# CCM_0005.net
KiCad netlist of a schematic drawn in EAGLE
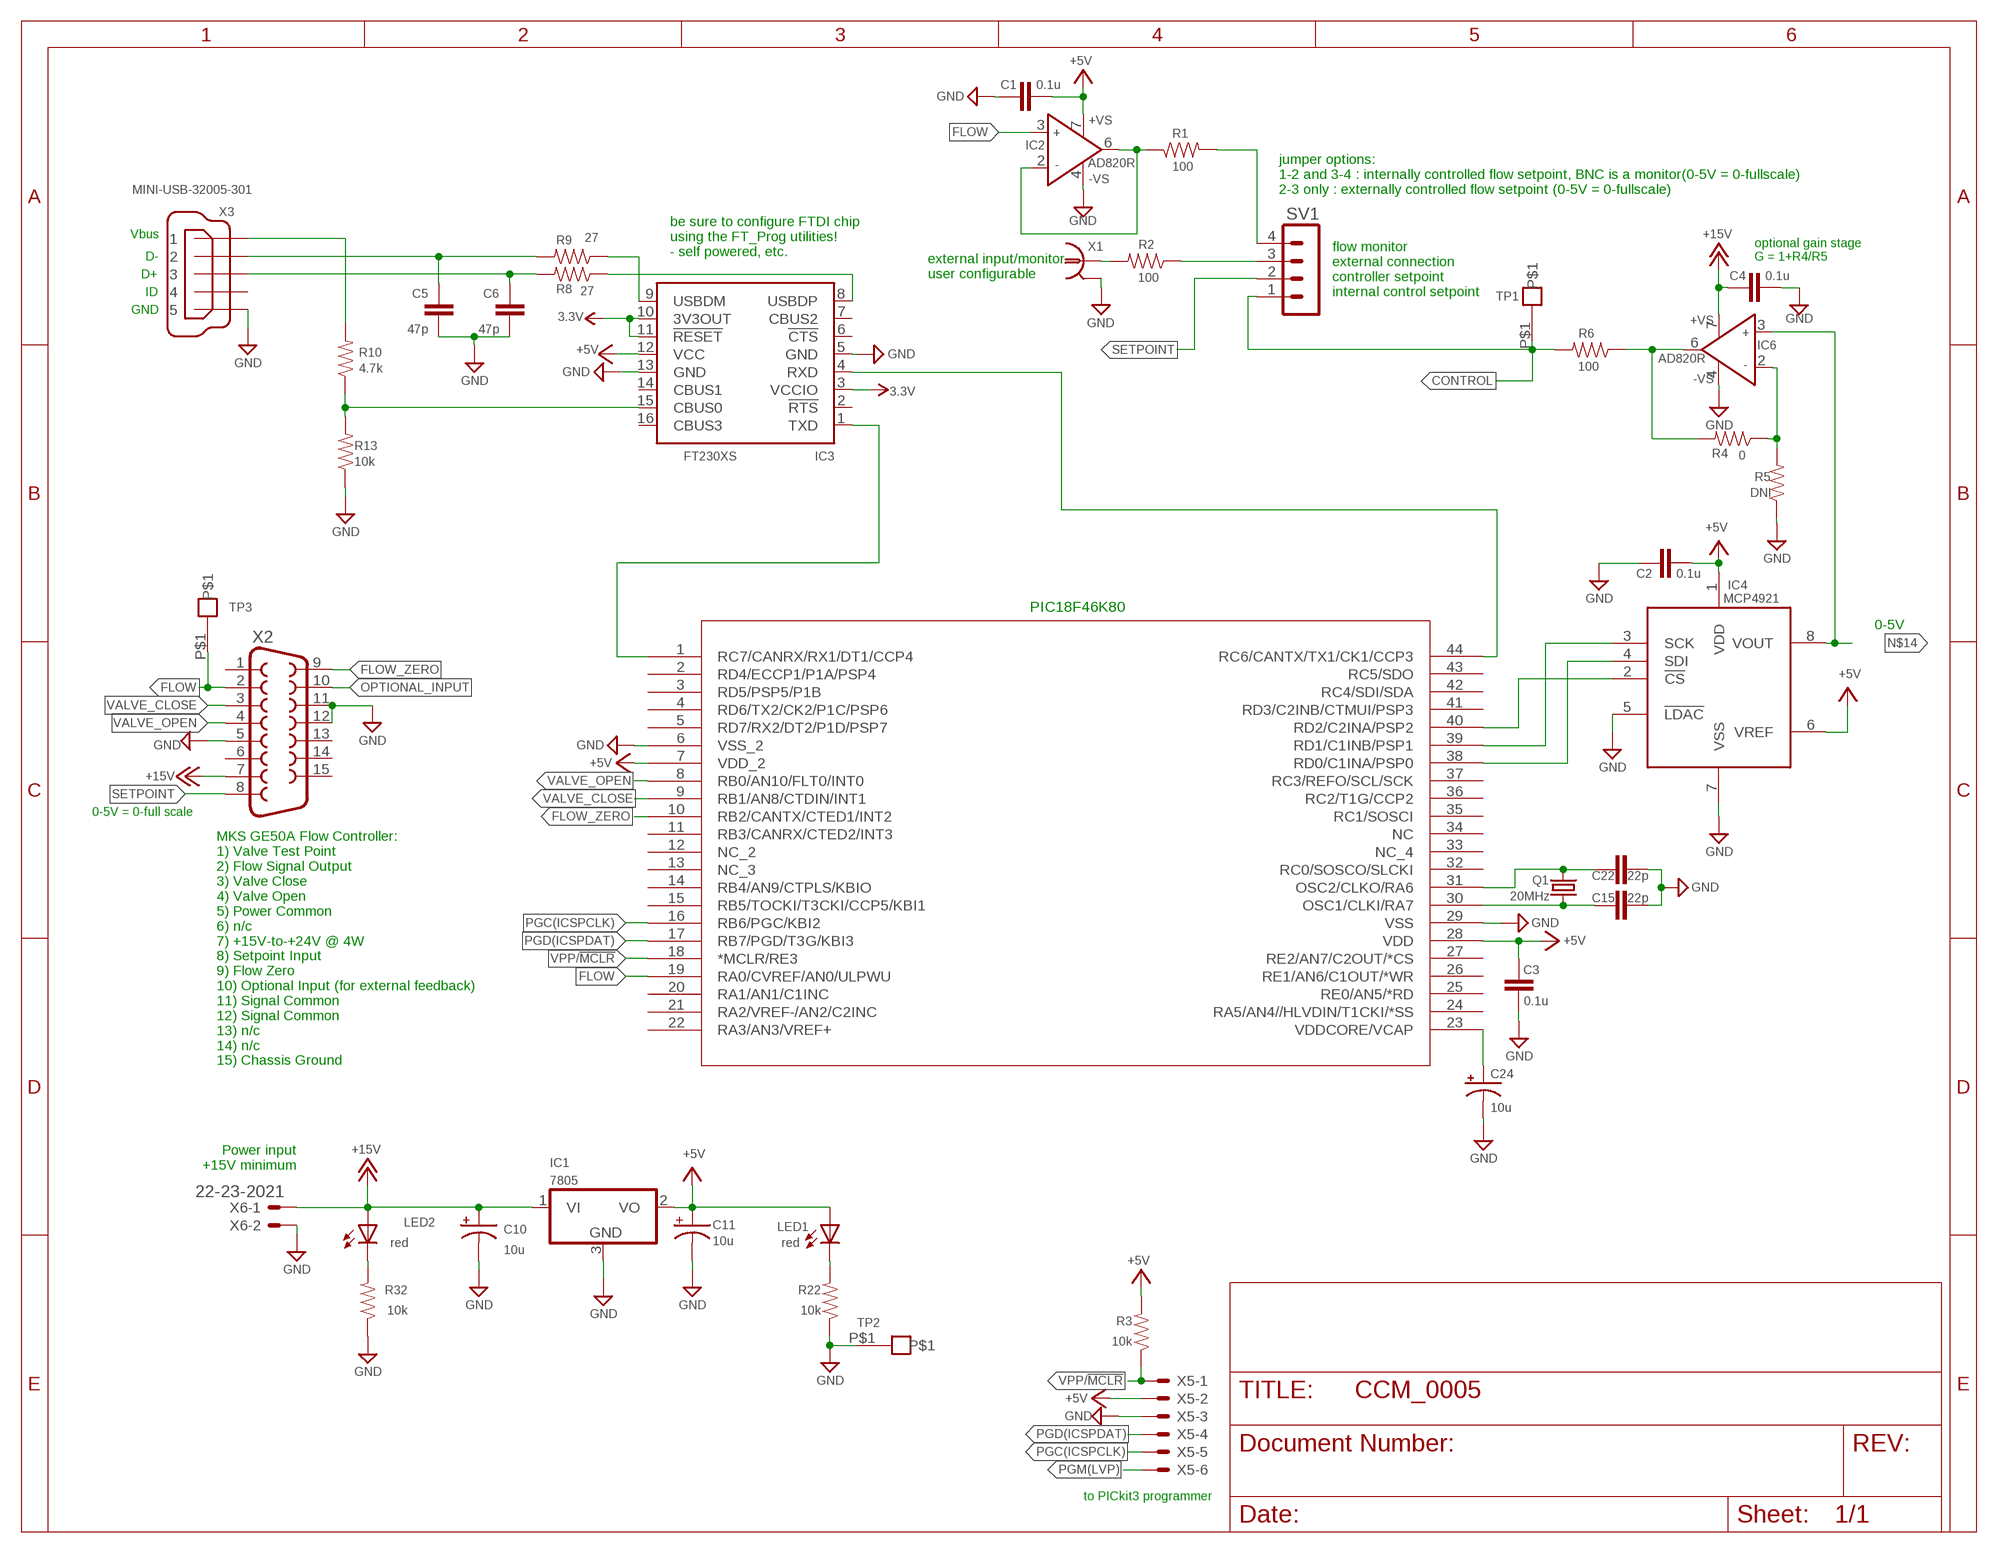
[diagram p0: schematic, sheet 1]

(export (version "E")
  (design (tool "Eeschema 10.0.6"))
  (components
    (comp (ref "C1")
      (value "0.1u")
      (footprint "eagle-import:0603-CAP")
      (libsource (lib "eagle-import") (part "CAP0603-CAP"))
    )
    (comp (ref "C2")
      (value "0.1u")
      (footprint "eagle-import:0603-CAP")
      (libsource (lib "eagle-import") (part "CAP0603-CAP"))
    )
    (comp (ref "C3")
      (value "0.1u")
      (footprint "eagle-import:0603-CAP")
      (libsource (lib "eagle-import") (part "CAP0603-CAP"))
    )
    (comp (ref "C4")
      (value "0.1u")
      (footprint "eagle-import:0603-CAP")
      (libsource (lib "eagle-import") (part "CAP0603-CAP"))
    )
    (comp (ref "C5")
      (value "47p")
      (footprint "eagle-import:0603-CAP")
      (libsource (lib "eagle-import") (part "CAP0603-CAP"))
    )
    (comp (ref "C6")
      (value "47p")
      (footprint "eagle-import:0603-CAP")
      (libsource (lib "eagle-import") (part "CAP0603-CAP"))
    )
    (comp (ref "C10")
      (value "10u")
      (footprint "eagle-import:EIA3216")
      (libsource (lib "eagle-import") (part "CAP_POL1206"))
    )
    (comp (ref "C11")
      (value "10u")
      (footprint "eagle-import:EIA3216")
      (libsource (lib "eagle-import") (part "CAP_POL1206"))
    )
    (comp (ref "C15")
      (value "22p")
      (footprint "eagle-import:0603-CAP")
      (libsource (lib "eagle-import") (part "CAP0603-CAP"))
    )
    (comp (ref "C22")
      (value "22p")
      (footprint "eagle-import:0603-CAP")
      (libsource (lib "eagle-import") (part "CAP0603-CAP"))
    )
    (comp (ref "C24")
      (value "10u")
      (footprint "eagle-import:EIA3216")
      (libsource (lib "eagle-import") (part "CAP_POL1206"))
    )
    (comp (ref "IC1")
      (value "7805")
      (footprint "eagle-import:TO252")
      (libsource (lib "eagle-import") (part "78DT24"))
    )
    (comp (ref "IC2")
      (value "AD820R")
      (footprint "eagle-import:SO8")
      (libsource (lib "eagle-import") (part "AD820R"))
    )
    (comp (ref "IC3")
      (value "FT230XS")
      (footprint "eagle-import:SSOP16")
      (libsource (lib "eagle-import") (part "FT230XS"))
    )
    (comp (ref "IC4")
      (value "MCP4921")
      (footprint "eagle-import:SO08")
      (libsource (lib "eagle-import") (part "MCP4921"))
    )
    (comp (ref "IC5")
      (value "PIC18F46K80")
      (footprint "eagle-import:TQFP44_MC")
      (libsource (lib "eagle-import") (part "PIC18F46K80"))
    )
    (comp (ref "IC6")
      (value "AD820R")
      (footprint "eagle-import:SO8")
      (libsource (lib "eagle-import") (part "AD820R"))
    )
    (comp (ref "LED1")
      (value "red")
      (footprint "eagle-import:CHIPLED_0603")
      (libsource (lib "eagle-import") (part "LEDCHIPLED_0603"))
    )
    (comp (ref "LED2")
      (value "red")
      (footprint "eagle-import:CHIPLED_0603")
      (libsource (lib "eagle-import") (part "LEDCHIPLED_0603"))
    )
    (comp (ref "Q1")
      (value "20MHz")
      (footprint "eagle-import:TC26V")
      (libsource (lib "eagle-import") (part "CRYSTALTC26V"))
    )
    (comp (ref "R1")
      (value "100")
      (footprint "eagle-import:0603-RES")
      (libsource (lib "eagle-import") (part "RESISTOR0603-RES"))
    )
    (comp (ref "R2")
      (value "100")
      (footprint "eagle-import:0603-RES")
      (libsource (lib "eagle-import") (part "RESISTOR0603-RES"))
    )
    (comp (ref "R3")
      (value "10k")
      (footprint "eagle-import:0603-RES")
      (libsource (lib "eagle-import") (part "RESISTOR0603-RES"))
    )
    (comp (ref "R4")
      (value "0")
      (footprint "eagle-import:0603-RES")
      (libsource (lib "eagle-import") (part "RESISTOR0603-RES"))
    )
    (comp (ref "R5")
      (value "DNI")
      (footprint "eagle-import:0603-RES")
      (libsource (lib "eagle-import") (part "RESISTOR0603-RES"))
    )
    (comp (ref "R6")
      (value "100")
      (footprint "eagle-import:0603-RES")
      (libsource (lib "eagle-import") (part "RESISTOR0603-RES"))
    )
    (comp (ref "R8")
      (value "27")
      (footprint "eagle-import:0603-RES")
      (libsource (lib "eagle-import") (part "RESISTOR0603-RES"))
    )
    (comp (ref "R9")
      (value "27")
      (footprint "eagle-import:0603-RES")
      (libsource (lib "eagle-import") (part "RESISTOR0603-RES"))
    )
    (comp (ref "R10")
      (value "4.7k")
      (footprint "eagle-import:0603-RES")
      (libsource (lib "eagle-import") (part "RESISTOR0603-RES"))
    )
    (comp (ref "R13")
      (value "10k")
      (footprint "eagle-import:0603-RES")
      (libsource (lib "eagle-import") (part "RESISTOR0603-RES"))
    )
    (comp (ref "R22")
      (value "10k")
      (footprint "eagle-import:0603-RES")
      (libsource (lib "eagle-import") (part "RESISTOR0603-RES"))
    )
    (comp (ref "R32")
      (value "10k")
      (footprint "eagle-import:0603-RES")
      (libsource (lib "eagle-import") (part "RESISTOR0603-RES"))
    )
    (comp (ref "SV1")
      (value "MA04-1")
      (footprint "eagle-import:MA04-1")
      (libsource (lib "eagle-import") (part "MA04-1"))
    )
    (comp (ref "TP1")
      (value "control")
      (footprint "eagle-import:TESTPOINT")
      (libsource (lib "eagle-import") (part "TESTPOINT"))
    )
    (comp (ref "TP2")
      (value "TESTPOINT")
      (footprint "eagle-import:TESTPOINT")
      (libsource (lib "eagle-import") (part "TESTPOINT"))
    )
    (comp (ref "TP3")
      (value "control")
      (footprint "eagle-import:TESTPOINT")
      (libsource (lib "eagle-import") (part "TESTPOINT"))
    )
    (comp (ref "X1")
      (value "1-227161-0")
      (footprint "eagle-import:AMP_227161")
      (fields (field (name "MF") "TYCO ELECTRONICS") (field (name "MPN") "1-227161"))
      (libsource (lib "eagle-import") (part "?2271611--0"))
    )
    (comp (ref "X2")
      (value "F15HP")
      (footprint "eagle-import:F15HP")
      (libsource (lib "eagle-import") (part "F15HP"))
    )
    (comp (ref "X3")
      (value "MINI-USB-32005-301")
      (footprint "eagle-import:32005-301")
      (libsource (lib "eagle-import") (part "MINI-USB-32005-301"))
    )
    (comp (ref "X5")
      (value "22-23-2061")
      (footprint "eagle-import:22-23-2061")
      (fields (field (name "MF") "MOLEX"))
      (libsource (lib "eagle-import") (part "22-23-2061"))
    )
    (comp (ref "X6")
      (value "22-23-2021")
      (footprint "eagle-import:22-23-2021")
      (fields (field (name "MF") "MOLEX"))
      (libsource (lib "eagle-import") (part "22-23-2021"))
    )
  )
  (nets
    (net (code "1") (name "+5V") (class "Default")
      (node (ref "C1") (pin "1") (pinfunction "1_1") (pintype "passive"))
      (node (ref "C11") (pin "A") (pinfunction "+_A") (pintype "passive"))
      (node (ref "C2") (pin "1") (pinfunction "1_1") (pintype "passive"))
      (node (ref "C3") (pin "1") (pinfunction "1_1") (pintype "passive"))
      (node (ref "IC1") (pin "2") (pinfunction "VO_2") (pintype "passive"))
      (node (ref "IC2") (pin "7") (pinfunction "+VS_7") (pintype "input"))
      (node (ref "IC3") (pin "12") (pinfunction "VCC_12") (pintype "power_in"))
      (node (ref "IC4") (pin "1") (pinfunction "VDD_1") (pintype "bidirectional"))
      (node (ref "IC4") (pin "6") (pinfunction "VREF_6") (pintype "bidirectional"))
      (node (ref "IC5") (pin "28") (pinfunction "VDD_28") (pintype "passive"))
      (node (ref "IC5") (pin "7") (pinfunction "VDD_2_7") (pintype "passive"))
      (node (ref "LED1") (pin "A") (pinfunction "A_A") (pintype "passive"))
      (node (ref "R3") (pin "2") (pinfunction "2_2") (pintype "passive"))
      (node (ref "X5") (pin "2") (pinfunction "S_2") (pintype "passive"))
    )
    (net (code "2") (name "+15V") (class "Default")
      (node (ref "C10") (pin "A") (pinfunction "+_A") (pintype "passive"))
      (node (ref "C4") (pin "2") (pinfunction "2_2") (pintype "passive"))
      (node (ref "IC1") (pin "1") (pinfunction "VI_1") (pintype "input"))
      (node (ref "IC6") (pin "7") (pinfunction "+VS_7") (pintype "input"))
      (node (ref "LED2") (pin "A") (pinfunction "A_A") (pintype "passive"))
      (node (ref "X2") (pin "7") (pinfunction "7_7") (pintype "passive"))
      (node (ref "X6") (pin "1") (pinfunction "S_1") (pintype "passive"))
    )
    (net (code "3") (name "/VPP{slash}~{MCLR}") (class "Default")
      (node (ref "IC5") (pin "18") (pinfunction "*MCLR/RE3_18") (pintype "passive"))
      (node (ref "R3") (pin "1") (pinfunction "1_1") (pintype "passive"))
      (node (ref "X5") (pin "1") (pinfunction "S_1") (pintype "passive"))
    )
    (net (code "4") (name "3.3V") (class "Default")
      (node (ref "IC3") (pin "10") (pinfunction "3V3OUT_10") (pintype "output"))
      (node (ref "IC3") (pin "11") (pinfunction "~{RESET}_11") (pintype "input"))
      (node (ref "IC3") (pin "3") (pinfunction "VCCIO_3") (pintype "power_in"))
    )
    (net (code "5") (name "CONTROL") (class "Default")
      (node (ref "R6") (pin "2") (pinfunction "2_2") (pintype "passive"))
      (node (ref "SV1") (pin "1") (pinfunction "1_1") (pintype "passive"))
      (node (ref "TP1") (pin "P$1") (pinfunction "P$1_P$1") (pintype "bidirectional"))
    )
    (net (code "6") (name "FLOW") (class "Default")
      (node (ref "IC2") (pin "3") (pinfunction "IN+_3") (pintype "input"))
      (node (ref "IC5") (pin "19") (pinfunction "RA0/CVREF/AN0/ULPWU_19") (pintype "passive"))
      (node (ref "TP3") (pin "P$1") (pinfunction "P$1_P$1") (pintype "bidirectional"))
      (node (ref "X2") (pin "2") (pinfunction "2_2") (pintype "passive"))
    )
    (net (code "7") (name "FLOW_ZERO") (class "Default")
      (node (ref "IC5") (pin "10") (pinfunction "RB2/CANTX/CTED1/INT2_10") (pintype "passive"))
      (node (ref "X2") (pin "9") (pinfunction "9_9") (pintype "passive"))
    )
    (net (code "8") (name "GND") (class "Default")
      (node (ref "C1") (pin "2") (pinfunction "2_2") (pintype "passive"))
      (node (ref "C10") (pin "C") (pinfunction "-_C") (pintype "passive"))
      (node (ref "C11") (pin "C") (pinfunction "-_C") (pintype "passive"))
      (node (ref "C15") (pin "1") (pinfunction "1_1") (pintype "passive"))
      (node (ref "C2") (pin "2") (pinfunction "2_2") (pintype "passive"))
      (node (ref "C22") (pin "1") (pinfunction "1_1") (pintype "passive"))
      (node (ref "C24") (pin "C") (pinfunction "-_C") (pintype "passive"))
      (node (ref "C3") (pin "2") (pinfunction "2_2") (pintype "passive"))
      (node (ref "C4") (pin "1") (pinfunction "1_1") (pintype "passive"))
      (node (ref "C5") (pin "2") (pinfunction "2_2") (pintype "passive"))
      (node (ref "C6") (pin "2") (pinfunction "2_2") (pintype "passive"))
      (node (ref "IC1") (pin "3") (pinfunction "GND_3") (pintype "passive"))
      (node (ref "IC2") (pin "4") (pinfunction "-VS_4") (pintype "input"))
      (node (ref "IC3") (pin "13") (pinfunction "GND_13") (pintype "power_in"))
      (node (ref "IC3") (pin "5") (pinfunction "GND_5") (pintype "power_in"))
      (node (ref "IC4") (pin "5") (pinfunction "~{LDAC}_5") (pintype "bidirectional"))
      (node (ref "IC4") (pin "7") (pinfunction "VSS_7") (pintype "bidirectional"))
      (node (ref "IC5") (pin "29") (pinfunction "VSS_29") (pintype "passive"))
      (node (ref "IC5") (pin "6") (pinfunction "VSS_2_6") (pintype "passive"))
      (node (ref "IC6") (pin "4") (pinfunction "-VS_4") (pintype "input"))
      (node (ref "R13") (pin "1") (pinfunction "1_1") (pintype "passive"))
      (node (ref "R22") (pin "1") (pinfunction "1_1") (pintype "passive"))
      (node (ref "R32") (pin "1") (pinfunction "1_1") (pintype "passive"))
      (node (ref "R5") (pin "1") (pinfunction "1_1") (pintype "passive"))
      (node (ref "TP2") (pin "P$1") (pinfunction "P$1_P$1") (pintype "bidirectional"))
      (node (ref "X1") (pin "2") (pinfunction "2_2") (pintype "passive"))
      (node (ref "X2") (pin "11") (pinfunction "11_11") (pintype "passive"))
      (node (ref "X2") (pin "12") (pinfunction "12_12") (pintype "passive"))
      (node (ref "X2") (pin "5") (pinfunction "5_5") (pintype "passive"))
      (node (ref "X3") (pin "5") (pinfunction "5_5") (pintype "passive"))
      (node (ref "X5") (pin "3") (pinfunction "S_3") (pintype "passive"))
      (node (ref "X6") (pin "2") (pinfunction "S_2") (pintype "passive"))
    )
    (net (code "9") (name "N$14") (class "Default")
      (node (ref "IC4") (pin "8") (pinfunction "VOUT_8") (pintype "bidirectional"))
      (node (ref "IC6") (pin "3") (pinfunction "IN+_3") (pintype "input"))
    )
    (net (code "10") (name "Net-(C5-Pad1)") (class "Default")
      (node (ref "C5") (pin "1") (pinfunction "1_1") (pintype "passive"))
      (node (ref "R9") (pin "2") (pinfunction "2_2") (pintype "passive"))
      (node (ref "X3") (pin "2") (pinfunction "2_2") (pintype "passive"))
    )
    (net (code "11") (name "Net-(C6-Pad1)") (class "Default")
      (node (ref "C6") (pin "1") (pinfunction "1_1") (pintype "passive"))
      (node (ref "R8") (pin "2") (pinfunction "2_2") (pintype "passive"))
      (node (ref "X3") (pin "3") (pinfunction "3_3") (pintype "passive"))
    )
    (net (code "12") (name "Net-(C24-+)") (class "Default")
      (node (ref "C24") (pin "A") (pinfunction "+_A") (pintype "passive"))
      (node (ref "IC5") (pin "23") (pinfunction "VDDCORE/VCAP_23") (pintype "passive"))
    )
    (net (code "13") (name "Net-(IC2-IN-)") (class "Default")
      (node (ref "IC2") (pin "2") (pinfunction "IN-_2") (pintype "input"))
      (node (ref "IC2") (pin "6") (pinfunction "OUT_6") (pintype "output"))
      (node (ref "R1") (pin "1") (pinfunction "1_1") (pintype "passive"))
    )
    (net (code "14") (name "Net-(IC3-CBUS0)") (class "Default")
      (node (ref "IC3") (pin "15") (pinfunction "CBUS0_15") (pintype "bidirectional"))
      (node (ref "R10") (pin "1") (pinfunction "1_1") (pintype "passive"))
      (node (ref "R13") (pin "2") (pinfunction "2_2") (pintype "passive"))
    )
    (net (code "15") (name "Net-(IC3-RXD)") (class "Default")
      (node (ref "IC3") (pin "4") (pinfunction "RXD_4") (pintype "input"))
      (node (ref "IC5") (pin "44") (pinfunction "RC6/CANTX/TX1/CK1/CCP3_44") (pintype "passive"))
    )
    (net (code "16") (name "Net-(IC3-TXD)") (class "Default")
      (node (ref "IC3") (pin "1") (pinfunction "TXD_1") (pintype "output"))
      (node (ref "IC5") (pin "1") (pinfunction "RC7/CANRX/RX1/DT1/CCP4_1") (pintype "passive"))
    )
    (net (code "17") (name "Net-(IC3-USBDM)") (class "Default")
      (node (ref "IC3") (pin "9") (pinfunction "USBDM_9") (pintype "input"))
      (node (ref "R9") (pin "1") (pinfunction "1_1") (pintype "passive"))
    )
    (net (code "18") (name "Net-(IC3-USBDP)") (class "Default")
      (node (ref "IC3") (pin "8") (pinfunction "USBDP_8") (pintype "input"))
      (node (ref "R8") (pin "1") (pinfunction "1_1") (pintype "passive"))
    )
    (net (code "19") (name "Net-(IC4-SCK)") (class "Default")
      (node (ref "IC4") (pin "3") (pinfunction "SCK_3") (pintype "bidirectional"))
      (node (ref "IC5") (pin "39") (pinfunction "RD1/C1INB/PSP1_39") (pintype "passive"))
    )
    (net (code "20") (name "Net-(IC4-SDI)") (class "Default")
      (node (ref "IC4") (pin "4") (pinfunction "SDI_4") (pintype "bidirectional"))
      (node (ref "IC5") (pin "38") (pinfunction "RD0/C1INA/PSP0_38") (pintype "passive"))
    )
    (net (code "21") (name "Net-(IC4-~{CS})") (class "Default")
      (node (ref "IC4") (pin "2") (pinfunction "~{CS}_2") (pintype "bidirectional"))
      (node (ref "IC5") (pin "40") (pinfunction "RD2/C2INA/PSP2_40") (pintype "passive"))
    )
    (net (code "22") (name "Net-(IC5-OSC1{slash}CLKI{slash}RA7)") (class "Default")
      (node (ref "C15") (pin "2") (pinfunction "2_2") (pintype "passive"))
      (node (ref "IC5") (pin "30") (pinfunction "OSC1/CLKI/RA7_30") (pintype "passive"))
      (node (ref "Q1") (pin "1") (pinfunction "1_1") (pintype "passive"))
    )
    (net (code "23") (name "Net-(IC5-OSC2{slash}CLKO{slash}RA6)") (class "Default")
      (node (ref "C22") (pin "2") (pinfunction "2_2") (pintype "passive"))
      (node (ref "IC5") (pin "31") (pinfunction "OSC2/CLKO/RA6_31") (pintype "passive"))
      (node (ref "Q1") (pin "2") (pinfunction "2_2") (pintype "passive"))
    )
    (net (code "24") (name "Net-(IC6-IN-)") (class "Default")
      (node (ref "IC6") (pin "2") (pinfunction "IN-_2") (pintype "input"))
      (node (ref "R4") (pin "1") (pinfunction "1_1") (pintype "passive"))
      (node (ref "R5") (pin "2") (pinfunction "2_2") (pintype "passive"))
    )
    (net (code "25") (name "Net-(IC6-OUT)") (class "Default")
      (node (ref "IC6") (pin "6") (pinfunction "OUT_6") (pintype "output"))
      (node (ref "R4") (pin "2") (pinfunction "2_2") (pintype "passive"))
      (node (ref "R6") (pin "1") (pinfunction "1_1") (pintype "passive"))
    )
    (net (code "26") (name "Net-(LED1-PadC)") (class "Default")
      (node (ref "LED1") (pin "C") (pinfunction "C_C") (pintype "passive"))
      (node (ref "R22") (pin "2") (pinfunction "2_2") (pintype "passive"))
    )
    (net (code "27") (name "Net-(LED2-PadC)") (class "Default")
      (node (ref "LED2") (pin "C") (pinfunction "C_C") (pintype "passive"))
      (node (ref "R32") (pin "2") (pinfunction "2_2") (pintype "passive"))
    )
    (net (code "28") (name "Net-(R1-Pad2)") (class "Default")
      (node (ref "R1") (pin "2") (pinfunction "2_2") (pintype "passive"))
      (node (ref "SV1") (pin "4") (pinfunction "4_4") (pintype "passive"))
    )
    (net (code "29") (name "Net-(R2-Pad1)") (class "Default")
      (node (ref "R2") (pin "1") (pinfunction "1_1") (pintype "passive"))
      (node (ref "SV1") (pin "3") (pinfunction "3_3") (pintype "passive"))
    )
    (net (code "30") (name "Net-(R2-Pad2)") (class "Default")
      (node (ref "R2") (pin "2") (pinfunction "2_2") (pintype "passive"))
      (node (ref "X1") (pin "1") (pinfunction "1_1") (pintype "passive"))
    )
    (net (code "31") (name "Net-(R10-Pad2)") (class "Default")
      (node (ref "R10") (pin "2") (pinfunction "2_2") (pintype "passive"))
      (node (ref "X3") (pin "1") (pinfunction "1_1") (pintype "passive"))
    )
    (net (code "32") (name "OPTIONAL_INPUT") (class "Default")
      (node (ref "X2") (pin "10") (pinfunction "10_10") (pintype "passive"))
    )
    (net (code "33") (name "PGC(ICSPCLK)") (class "Default")
      (node (ref "IC5") (pin "16") (pinfunction "RB6/PGC/KBI2_16") (pintype "passive"))
      (node (ref "X5") (pin "5") (pinfunction "S_5") (pintype "passive"))
    )
    (net (code "34") (name "PGD(ICSPDAT)") (class "Default")
      (node (ref "IC5") (pin "17") (pinfunction "RB7/PGD/T3G/KBI3_17") (pintype "passive"))
      (node (ref "X5") (pin "4") (pinfunction "S_4") (pintype "passive"))
    )
    (net (code "35") (name "PGM(LVP)") (class "Default")
      (node (ref "X5") (pin "6") (pinfunction "S_6") (pintype "passive"))
    )
    (net (code "36") (name "SETPOINT") (class "Default")
      (node (ref "SV1") (pin "2") (pinfunction "2_2") (pintype "passive"))
      (node (ref "X2") (pin "8") (pinfunction "8_8") (pintype "passive"))
    )
    (net (code "37") (name "VALVE_CLOSE") (class "Default")
      (node (ref "IC5") (pin "9") (pinfunction "RB1/AN8/CTDIN/INT1_9") (pintype "passive"))
      (node (ref "X2") (pin "3") (pinfunction "3_3") (pintype "passive"))
    )
    (net (code "38") (name "VALVE_OPEN") (class "Default")
      (node (ref "IC5") (pin "8") (pinfunction "RB0/AN10/FLT0/INT0_8") (pintype "passive"))
      (node (ref "X2") (pin "4") (pinfunction "4_4") (pintype "passive"))
    )
    (net (code "39") (name "unconnected-(IC3-CBUS1-Pad14)") (class "Default")
      (node (ref "IC3") (pin "14") (pinfunction "CBUS1_14") (pintype "bidirectional"))
    )
    (net (code "40") (name "unconnected-(IC3-CBUS2-Pad7)") (class "Default")
      (node (ref "IC3") (pin "7") (pinfunction "CBUS2_7") (pintype "bidirectional"))
    )
    (net (code "41") (name "unconnected-(IC3-CBUS3-Pad16)") (class "Default")
      (node (ref "IC3") (pin "16") (pinfunction "CBUS3_16") (pintype "bidirectional"))
    )
    (net (code "42") (name "unconnected-(IC3-~{CTS}-Pad6)") (class "Default")
      (node (ref "IC3") (pin "6") (pinfunction "~{CTS}_6") (pintype "input"))
    )
    (net (code "43") (name "unconnected-(IC3-~{RTS}-Pad2)") (class "Default")
      (node (ref "IC3") (pin "2") (pinfunction "~{RTS}_2") (pintype "output"))
    )
    (net (code "44") (name "unconnected-(IC5-NC-Pad34)") (class "Default")
      (node (ref "IC5") (pin "34") (pinfunction "NC_34") (pintype "passive"))
    )
    (net (code "45") (name "unconnected-(IC5-NC_2-Pad12)") (class "Default")
      (node (ref "IC5") (pin "12") (pinfunction "NC_2_12") (pintype "passive"))
    )
    (net (code "46") (name "unconnected-(IC5-NC_3-Pad13)") (class "Default")
      (node (ref "IC5") (pin "13") (pinfunction "NC_3_13") (pintype "passive"))
    )
    (net (code "47") (name "unconnected-(IC5-NC_4-Pad33)") (class "Default")
      (node (ref "IC5") (pin "33") (pinfunction "NC_4_33") (pintype "passive"))
    )
    (net (code "48") (name "unconnected-(IC5-RA1{slash}AN1{slash}C1INC-Pad20)") (class "Default")
      (node (ref "IC5") (pin "20") (pinfunction "RA1/AN1/C1INC_20") (pintype "passive"))
    )
    (net (code "49") (name "unconnected-(IC5-RA2{slash}VREF-{slash}AN2{slash}C2INC-Pad21)") (class "Default")
      (node (ref "IC5") (pin "21") (pinfunction "RA2/VREF-/AN2/C2INC_21") (pintype "passive"))
    )
    (net (code "50") (name "unconnected-(IC5-RA3{slash}AN3{slash}VREF+-Pad22)") (class "Default")
      (node (ref "IC5") (pin "22") (pinfunction "RA3/AN3/VREF+_22") (pintype "passive"))
    )
    (net (code "51") (name "unconnected-(IC5-RA5{slash}AN4{slash}{slash}HLVDIN{slash}T1CKI{slash}*SS-Pad24)") (class "Default")
      (node (ref "IC5") (pin "24") (pinfunction "RA5/AN4//HLVDIN/T1CKI/*SS_24") (pintype "passive"))
    )
    (net (code "52") (name "unconnected-(IC5-RB3{slash}CANRX{slash}CTED2{slash}INT3-Pad11)") (class "Default")
      (node (ref "IC5") (pin "11") (pinfunction "RB3/CANRX/CTED2/INT3_11") (pintype "passive"))
    )
    (net (code "53") (name "unconnected-(IC5-RB4{slash}AN9{slash}CTPLS{slash}KBIO-Pad14)") (class "Default")
      (node (ref "IC5") (pin "14") (pinfunction "RB4/AN9/CTPLS/KBIO_14") (pintype "passive"))
    )
    (net (code "54") (name "unconnected-(IC5-RB5{slash}TOCKI{slash}T3CKI{slash}CCP5{slash}KBI1-Pad15)") (class "Default")
      (node (ref "IC5") (pin "15") (pinfunction "RB5/TOCKI/T3CKI/CCP5/KBI1_15") (pintype "passive"))
    )
    (net (code "55") (name "unconnected-(IC5-RC0{slash}SOSCO{slash}SLCKI-Pad32)") (class "Default")
      (node (ref "IC5") (pin "32") (pinfunction "RC0/SOSCO/SLCKI_32") (pintype "passive"))
    )
    (net (code "56") (name "unconnected-(IC5-RC1{slash}SOSCI-Pad35)") (class "Default")
      (node (ref "IC5") (pin "35") (pinfunction "RC1/SOSCI_35") (pintype "passive"))
    )
    (net (code "57") (name "unconnected-(IC5-RC2{slash}T1G{slash}CCP2-Pad36)") (class "Default")
      (node (ref "IC5") (pin "36") (pinfunction "RC2/T1G/CCP2_36") (pintype "passive"))
    )
    (net (code "58") (name "unconnected-(IC5-RC3{slash}REFO{slash}SCL{slash}SCK-Pad37)") (class "Default")
      (node (ref "IC5") (pin "37") (pinfunction "RC3/REFO/SCL/SCK_37") (pintype "passive"))
    )
    (net (code "59") (name "unconnected-(IC5-RC4{slash}SDI{slash}SDA-Pad42)") (class "Default")
      (node (ref "IC5") (pin "42") (pinfunction "RC4/SDI/SDA_42") (pintype "passive"))
    )
    (net (code "60") (name "unconnected-(IC5-RC5{slash}SDO-Pad43)") (class "Default")
      (node (ref "IC5") (pin "43") (pinfunction "RC5/SDO_43") (pintype "passive"))
    )
    (net (code "61") (name "unconnected-(IC5-RD3{slash}C2INB{slash}CTMUI{slash}PSP3-Pad41)") (class "Default")
      (node (ref "IC5") (pin "41") (pinfunction "RD3/C2INB/CTMUI/PSP3_41") (pintype "passive"))
    )
    (net (code "62") (name "unconnected-(IC5-RD4{slash}ECCP1{slash}P1A{slash}PSP4-Pad2)") (class "Default")
      (node (ref "IC5") (pin "2") (pinfunction "RD4/ECCP1/P1A/PSP4_2") (pintype "passive"))
    )
    (net (code "63") (name "unconnected-(IC5-RD5{slash}PSP5{slash}P1B-Pad3)") (class "Default")
      (node (ref "IC5") (pin "3") (pinfunction "RD5/PSP5/P1B_3") (pintype "passive"))
    )
    (net (code "64") (name "unconnected-(IC5-RD6{slash}TX2{slash}CK2{slash}P1C{slash}PSP6-Pad4)") (class "Default")
      (node (ref "IC5") (pin "4") (pinfunction "RD6/TX2/CK2/P1C/PSP6_4") (pintype "passive"))
    )
    (net (code "65") (name "unconnected-(IC5-RD7{slash}RX2{slash}DT2{slash}P1D{slash}PSP7-Pad5)") (class "Default")
      (node (ref "IC5") (pin "5") (pinfunction "RD7/RX2/DT2/P1D/PSP7_5") (pintype "passive"))
    )
    (net (code "66") (name "unconnected-(IC5-RE0{slash}AN5{slash}*RD-Pad25)") (class "Default")
      (node (ref "IC5") (pin "25") (pinfunction "RE0/AN5/*RD_25") (pintype "passive"))
    )
    (net (code "67") (name "unconnected-(IC5-RE1{slash}AN6{slash}C1OUT{slash}*WR-Pad26)") (class "Default")
      (node (ref "IC5") (pin "26") (pinfunction "RE1/AN6/C1OUT/*WR_26") (pintype "passive"))
    )
    (net (code "68") (name "unconnected-(IC5-RE2{slash}AN7{slash}C2OUT{slash}*CS-Pad27)") (class "Default")
      (node (ref "IC5") (pin "27") (pinfunction "RE2/AN7/C2OUT/*CS_27") (pintype "passive"))
    )
    (net (code "69") (name "unconnected-(X2-Pad1)") (class "Default")
      (node (ref "X2") (pin "1") (pinfunction "1_1") (pintype "passive"))
    )
    (net (code "70") (name "unconnected-(X2-Pad6)") (class "Default")
      (node (ref "X2") (pin "6") (pinfunction "6_6") (pintype "passive"))
    )
    (net (code "71") (name "unconnected-(X2-Pad13)") (class "Default")
      (node (ref "X2") (pin "13") (pinfunction "13_13") (pintype "passive"))
    )
    (net (code "72") (name "unconnected-(X2-Pad14)") (class "Default")
      (node (ref "X2") (pin "14") (pinfunction "14_14") (pintype "passive"))
    )
    (net (code "73") (name "unconnected-(X2-Pad15)") (class "Default")
      (node (ref "X2") (pin "15") (pinfunction "15_15") (pintype "passive"))
    )
    (net (code "74") (name "unconnected-(X3-Pad4)") (class "Default")
      (node (ref "X3") (pin "4") (pinfunction "4_4") (pintype "passive"))
    )
  )
)
